# Grove_-_RGB_LED_Ring_20-WS2813_Mini.net
KiCad netlist of a schematic drawn in EAGLE
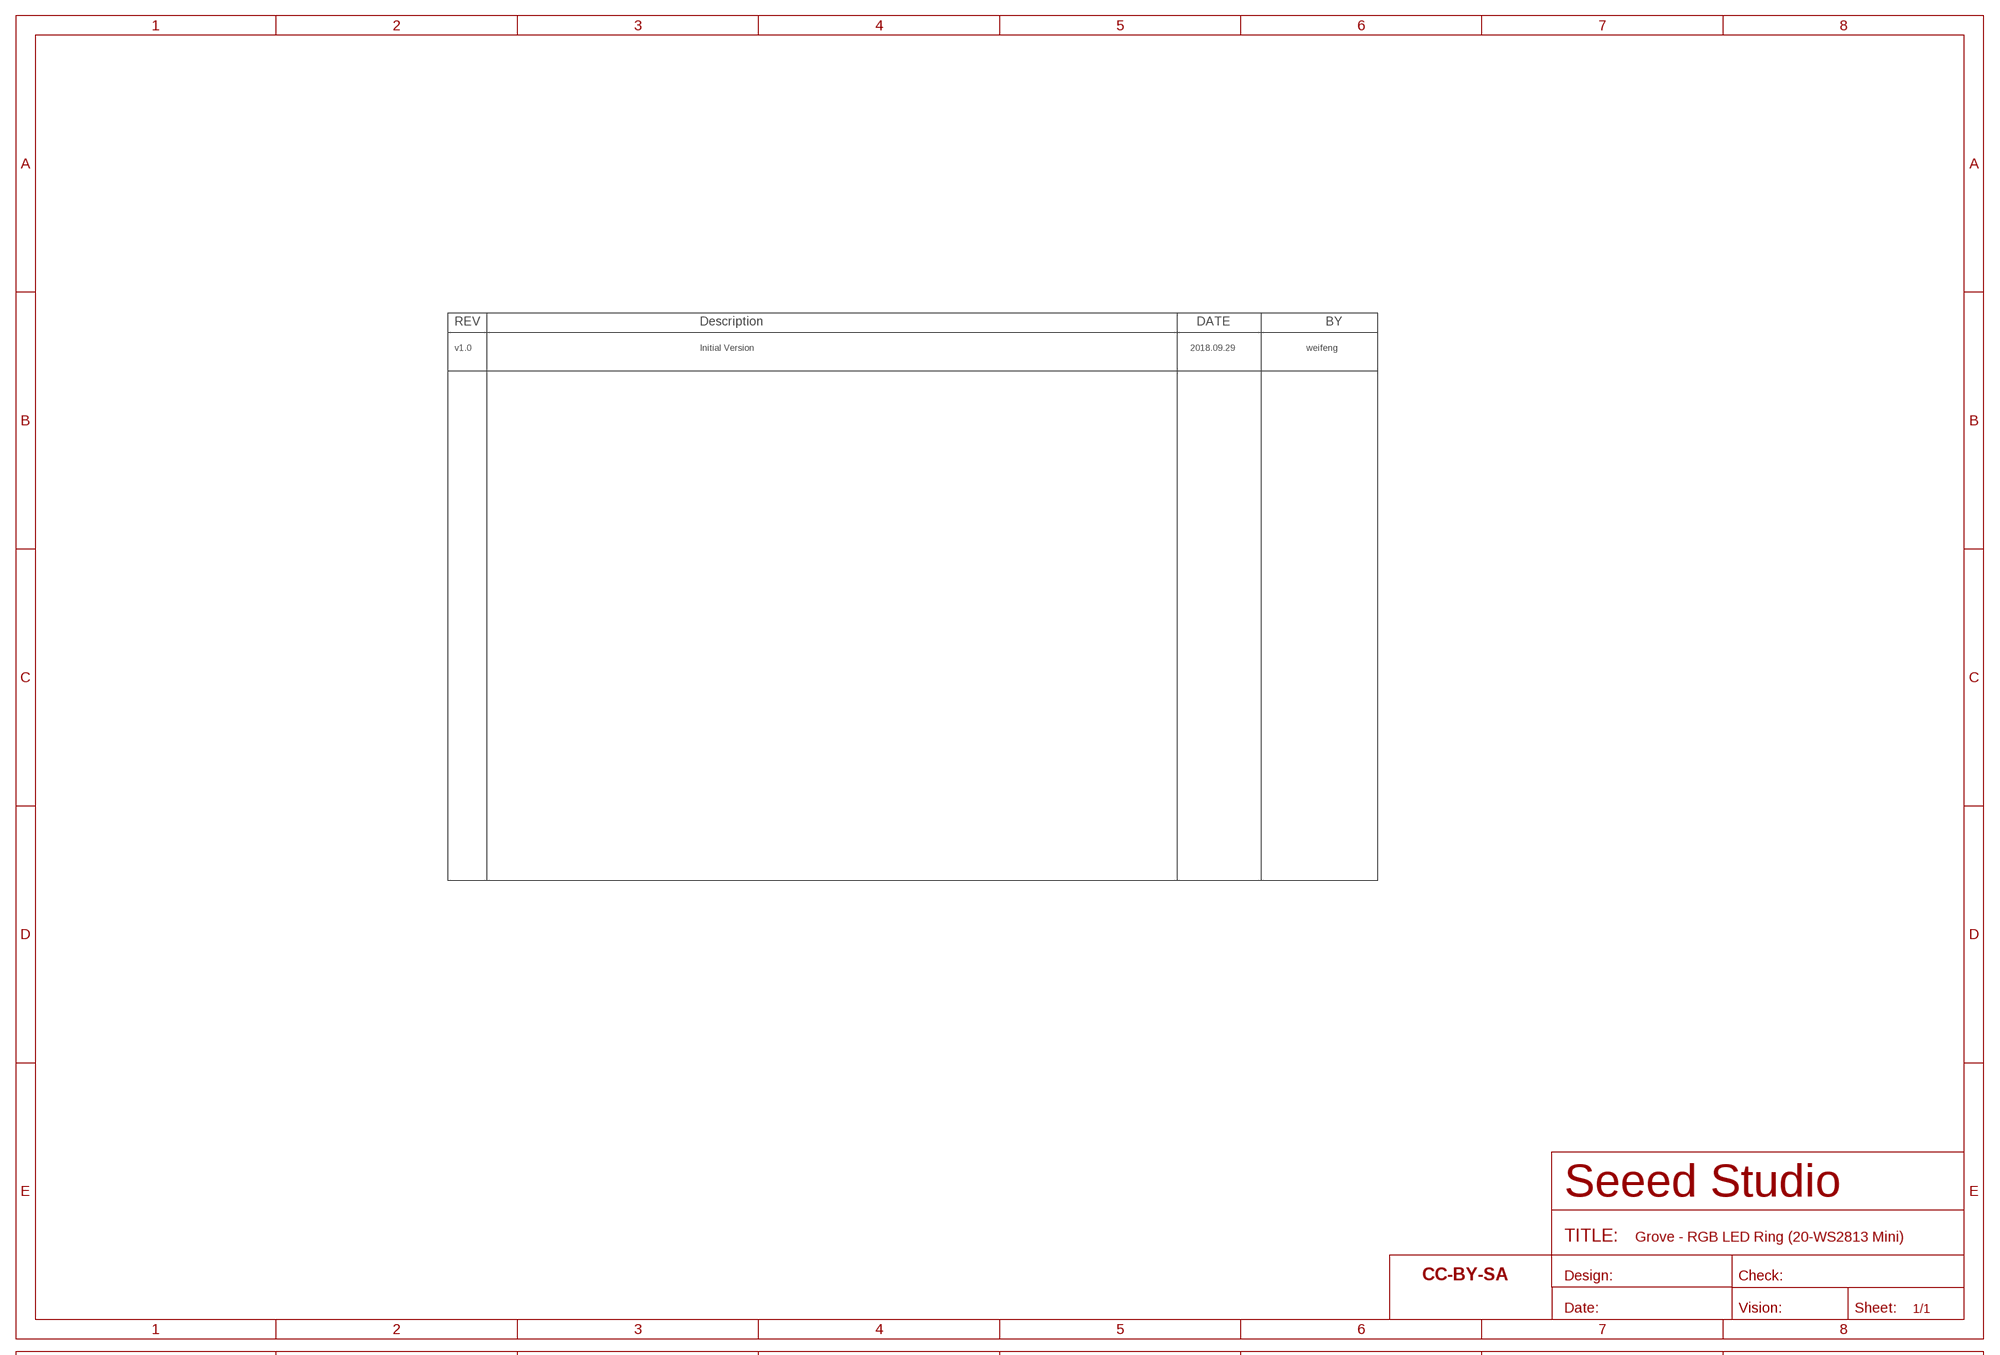
[diagram p0: schematic, sheet 1, part 1 of 2]
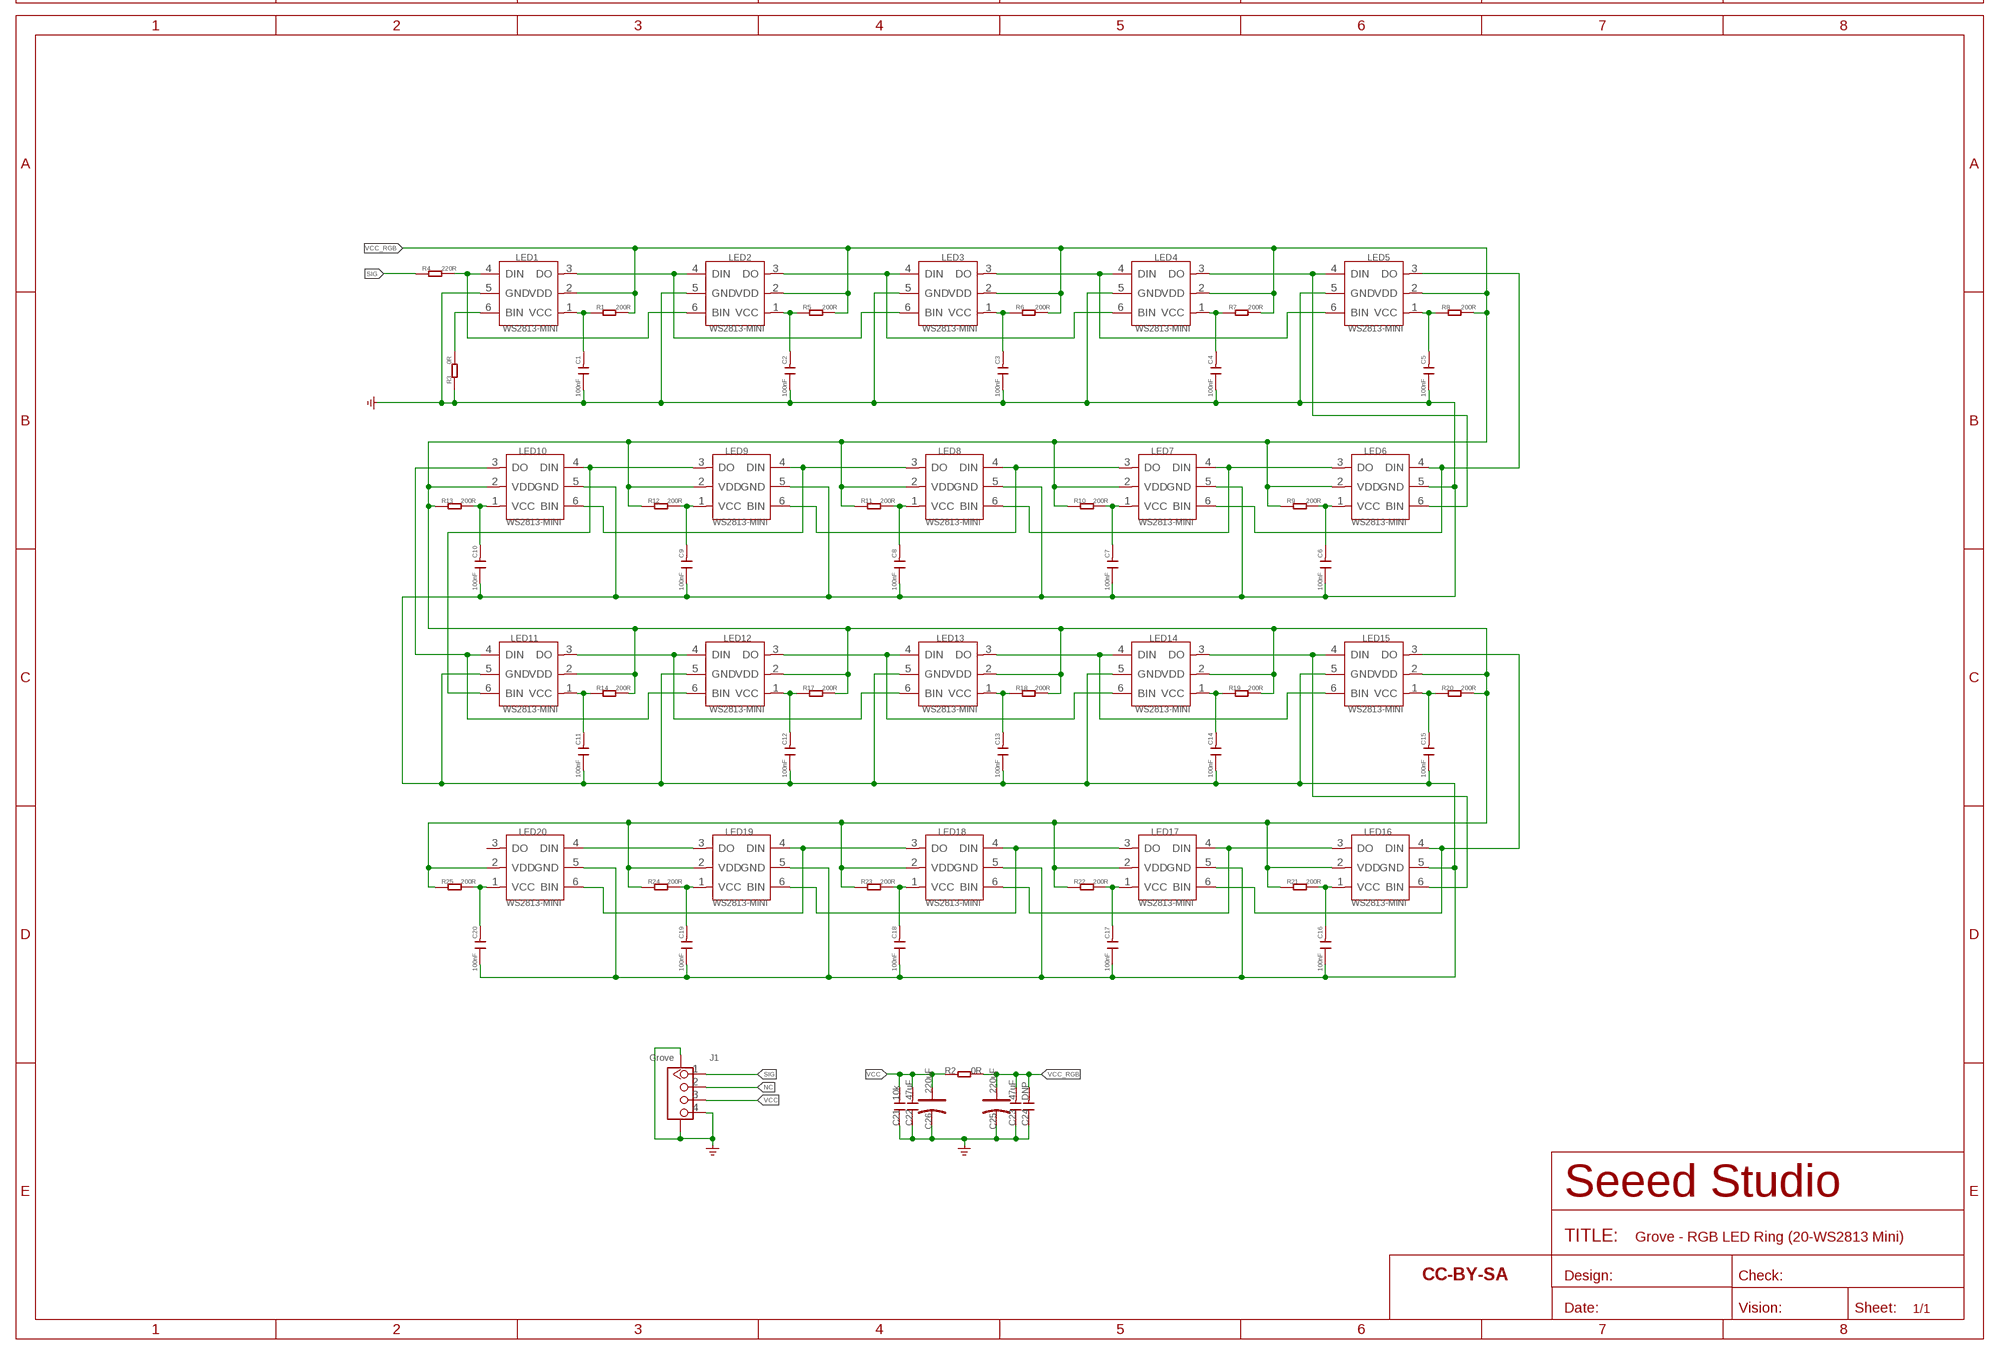
[diagram p1: schematic, sheet 1, part 2 of 2]

(export (version "E")
  (design (tool "Eeschema 10.0.6"))
  (components
    (comp (ref "C1")
      (value "100nF")
      (footprint "eagle-import:C0603")
      (libsource (lib "eagle-import") (part "C-0603"))
    )
    (comp (ref "C2")
      (value "100nF")
      (footprint "eagle-import:C0603")
      (libsource (lib "eagle-import") (part "C-0603"))
    )
    (comp (ref "C3")
      (value "100nF")
      (footprint "eagle-import:C0603")
      (libsource (lib "eagle-import") (part "C-0603"))
    )
    (comp (ref "C4")
      (value "100nF")
      (footprint "eagle-import:C0603")
      (libsource (lib "eagle-import") (part "C-0603"))
    )
    (comp (ref "C5")
      (value "100nF")
      (footprint "eagle-import:C0603")
      (libsource (lib "eagle-import") (part "C-0603"))
    )
    (comp (ref "C6")
      (value "100nF")
      (footprint "eagle-import:C0603")
      (libsource (lib "eagle-import") (part "C-0603"))
    )
    (comp (ref "C7")
      (value "100nF")
      (footprint "eagle-import:C0603")
      (libsource (lib "eagle-import") (part "C-0603"))
    )
    (comp (ref "C8")
      (value "100nF")
      (footprint "eagle-import:C0603")
      (libsource (lib "eagle-import") (part "C-0603"))
    )
    (comp (ref "C9")
      (value "100nF")
      (footprint "eagle-import:C0603")
      (libsource (lib "eagle-import") (part "C-0603"))
    )
    (comp (ref "C10")
      (value "100nF")
      (footprint "eagle-import:C0603")
      (libsource (lib "eagle-import") (part "C-0603"))
    )
    (comp (ref "C11")
      (value "100nF")
      (footprint "eagle-import:C0603")
      (libsource (lib "eagle-import") (part "C-0603"))
    )
    (comp (ref "C12")
      (value "100nF")
      (footprint "eagle-import:C0603")
      (libsource (lib "eagle-import") (part "C-0603"))
    )
    (comp (ref "C13")
      (value "100nF")
      (footprint "eagle-import:C0603")
      (libsource (lib "eagle-import") (part "C-0603"))
    )
    (comp (ref "C14")
      (value "100nF")
      (footprint "eagle-import:C0603")
      (libsource (lib "eagle-import") (part "C-0603"))
    )
    (comp (ref "C15")
      (value "100nF")
      (footprint "eagle-import:C0603")
      (libsource (lib "eagle-import") (part "C-0603"))
    )
    (comp (ref "C16")
      (value "100nF")
      (footprint "eagle-import:C0603")
      (libsource (lib "eagle-import") (part "C-0603"))
    )
    (comp (ref "C17")
      (value "100nF")
      (footprint "eagle-import:C0603")
      (libsource (lib "eagle-import") (part "C-0603"))
    )
    (comp (ref "C18")
      (value "100nF")
      (footprint "eagle-import:C0603")
      (libsource (lib "eagle-import") (part "C-0603"))
    )
    (comp (ref "C19")
      (value "100nF")
      (footprint "eagle-import:C0603")
      (libsource (lib "eagle-import") (part "C-0603"))
    )
    (comp (ref "C20")
      (value "100nF")
      (footprint "eagle-import:C0603")
      (libsource (lib "eagle-import") (part "C-0603"))
    )
    (comp (ref "C21")
      (value "10k")
      (footprint "eagle-import:C0603@1")
      (libsource (lib "eagle-import") (part "CAP-0603"))
    )
    (comp (ref "C22")
      (value "47uF")
      (footprint "eagle-import:C0805")
      (libsource (lib "eagle-import") (part "CAP-0805"))
    )
    (comp (ref "C23")
      (value "47uF")
      (footprint "eagle-import:C0805")
      (libsource (lib "eagle-import") (part "CAP-0805"))
    )
    (comp (ref "C24")
      (value "DNP")
      (footprint "eagle-import:C0603@1")
      (libsource (lib "eagle-import") (part "CAP-0603"))
    )
    (comp (ref "C25")
      (value "220uF")
      (footprint "eagle-import:AVX-B")
      (libsource (lib "eagle-import") (part "CAP-POLAR-AVX-B"))
    )
    (comp (ref "C26")
      (value "220uF")
      (footprint "eagle-import:AVX-B")
      (libsource (lib "eagle-import") (part "CAP-POLAR-AVX-B"))
    )
    (comp (ref "FR1")
      (value "SEEEDSTUDIO-OPEN-SCH-FRAME-BIG")
      (footprint "eagle-import:SEEEDSTUDIO-PCB-FRAME")
      (libsource (lib "eagle-import") (part "SEEEDSTUDIO-OPEN-SCH-FRAME-BIG"))
    )
    (comp (ref "FR2")
      (value "SEEEDSTUDIO-OPEN-SCH-FRAME-BIG")
      (footprint "eagle-import:SEEEDSTUDIO-PCB-FRAME")
      (libsource (lib "eagle-import") (part "SEEEDSTUDIO-OPEN-SCH-FRAME-BIG"))
    )
    (comp (ref "J1")
      (value "Grove")
      (footprint "eagle-import:HW4-SMD-2.0")
      (libsource (lib "eagle-import") (part "GROVE-CONNECTOR-SMD'DD'"))
    )
    (comp (ref "LED1")
      (value "WS2813-MINI")
      (footprint "eagle-import:LED6-1.1-3.5X3.5X0.95MM")
      (libsource (lib "eagle-import") (part "LED-RGB-6P-WS2813"))
    )
    (comp (ref "LED2")
      (value "WS2813-MINI")
      (footprint "eagle-import:LED6-1.1-3.5X3.5X0.95MM")
      (libsource (lib "eagle-import") (part "LED-RGB-6P-WS2813"))
    )
    (comp (ref "LED3")
      (value "WS2813-MINI")
      (footprint "eagle-import:LED6-1.1-3.5X3.5X0.95MM")
      (libsource (lib "eagle-import") (part "LED-RGB-6P-WS2813"))
    )
    (comp (ref "LED4")
      (value "WS2813-MINI")
      (footprint "eagle-import:LED6-1.1-3.5X3.5X0.95MM")
      (libsource (lib "eagle-import") (part "LED-RGB-6P-WS2813"))
    )
    (comp (ref "LED5")
      (value "WS2813-MINI")
      (footprint "eagle-import:LED6-1.1-3.5X3.5X0.95MM")
      (libsource (lib "eagle-import") (part "LED-RGB-6P-WS2813"))
    )
    (comp (ref "LED6")
      (value "WS2813-MINI")
      (footprint "eagle-import:LED6-1.1-3.5X3.5X0.95MM")
      (libsource (lib "eagle-import") (part "LED-RGB-6P-WS2813"))
    )
    (comp (ref "LED7")
      (value "WS2813-MINI")
      (footprint "eagle-import:LED6-1.1-3.5X3.5X0.95MM")
      (libsource (lib "eagle-import") (part "LED-RGB-6P-WS2813"))
    )
    (comp (ref "LED8")
      (value "WS2813-MINI")
      (footprint "eagle-import:LED6-1.1-3.5X3.5X0.95MM")
      (libsource (lib "eagle-import") (part "LED-RGB-6P-WS2813"))
    )
    (comp (ref "LED9")
      (value "WS2813-MINI")
      (footprint "eagle-import:LED6-1.1-3.5X3.5X0.95MM")
      (libsource (lib "eagle-import") (part "LED-RGB-6P-WS2813"))
    )
    (comp (ref "LED10")
      (value "WS2813-MINI")
      (footprint "eagle-import:LED6-1.1-3.5X3.5X0.95MM")
      (libsource (lib "eagle-import") (part "LED-RGB-6P-WS2813"))
    )
    (comp (ref "LED11")
      (value "WS2813-MINI")
      (footprint "eagle-import:LED6-1.1-3.5X3.5X0.95MM")
      (libsource (lib "eagle-import") (part "LED-RGB-6P-WS2813"))
    )
    (comp (ref "LED12")
      (value "WS2813-MINI")
      (footprint "eagle-import:LED6-1.1-3.5X3.5X0.95MM")
      (libsource (lib "eagle-import") (part "LED-RGB-6P-WS2813"))
    )
    (comp (ref "LED13")
      (value "WS2813-MINI")
      (footprint "eagle-import:LED6-1.1-3.5X3.5X0.95MM")
      (libsource (lib "eagle-import") (part "LED-RGB-6P-WS2813"))
    )
    (comp (ref "LED14")
      (value "WS2813-MINI")
      (footprint "eagle-import:LED6-1.1-3.5X3.5X0.95MM")
      (libsource (lib "eagle-import") (part "LED-RGB-6P-WS2813"))
    )
    (comp (ref "LED15")
      (value "WS2813-MINI")
      (footprint "eagle-import:LED6-1.1-3.5X3.5X0.95MM")
      (libsource (lib "eagle-import") (part "LED-RGB-6P-WS2813"))
    )
    (comp (ref "LED16")
      (value "WS2813-MINI")
      (footprint "eagle-import:LED6-1.1-3.5X3.5X0.95MM")
      (libsource (lib "eagle-import") (part "LED-RGB-6P-WS2813"))
    )
    (comp (ref "LED17")
      (value "WS2813-MINI")
      (footprint "eagle-import:LED6-1.1-3.5X3.5X0.95MM")
      (libsource (lib "eagle-import") (part "LED-RGB-6P-WS2813"))
    )
    (comp (ref "LED18")
      (value "WS2813-MINI")
      (footprint "eagle-import:LED6-1.1-3.5X3.5X0.95MM")
      (libsource (lib "eagle-import") (part "LED-RGB-6P-WS2813"))
    )
    (comp (ref "LED19")
      (value "WS2813-MINI")
      (footprint "eagle-import:LED6-1.1-3.5X3.5X0.95MM")
      (libsource (lib "eagle-import") (part "LED-RGB-6P-WS2813"))
    )
    (comp (ref "LED20")
      (value "WS2813-MINI")
      (footprint "eagle-import:LED6-1.1-3.5X3.5X0.95MM")
      (libsource (lib "eagle-import") (part "LED-RGB-6P-WS2813"))
    )
    (comp (ref "R1")
      (value "200R")
      (footprint "eagle-import:R0603")
      (libsource (lib "eagle-import") (part "R-0603"))
    )
    (comp (ref "R2")
      (value "0R")
      (footprint "eagle-import:R0805")
      (libsource (lib "eagle-import") (part "RES-0805"))
    )
    (comp (ref "R3")
      (value "0R")
      (footprint "eagle-import:R0603")
      (libsource (lib "eagle-import") (part "R-0603"))
    )
    (comp (ref "R4")
      (value "220R")
      (footprint "eagle-import:R0603")
      (libsource (lib "eagle-import") (part "R-0603"))
    )
    (comp (ref "R5")
      (value "200R")
      (footprint "eagle-import:R0603")
      (libsource (lib "eagle-import") (part "R-0603"))
    )
    (comp (ref "R6")
      (value "200R")
      (footprint "eagle-import:R0603")
      (libsource (lib "eagle-import") (part "R-0603"))
    )
    (comp (ref "R7")
      (value "200R")
      (footprint "eagle-import:R0603")
      (libsource (lib "eagle-import") (part "R-0603"))
    )
    (comp (ref "R8")
      (value "200R")
      (footprint "eagle-import:R0603")
      (libsource (lib "eagle-import") (part "R-0603"))
    )
    (comp (ref "R9")
      (value "200R")
      (footprint "eagle-import:R0603")
      (libsource (lib "eagle-import") (part "R-0603"))
    )
    (comp (ref "R10")
      (value "200R")
      (footprint "eagle-import:R0603")
      (libsource (lib "eagle-import") (part "R-0603"))
    )
    (comp (ref "R11")
      (value "200R")
      (footprint "eagle-import:R0603")
      (libsource (lib "eagle-import") (part "R-0603"))
    )
    (comp (ref "R12")
      (value "200R")
      (footprint "eagle-import:R0603")
      (libsource (lib "eagle-import") (part "R-0603"))
    )
    (comp (ref "R13")
      (value "200R")
      (footprint "eagle-import:R0603")
      (libsource (lib "eagle-import") (part "R-0603"))
    )
    (comp (ref "R14")
      (value "200R")
      (footprint "eagle-import:R0603")
      (libsource (lib "eagle-import") (part "R-0603"))
    )
    (comp (ref "R17")
      (value "200R")
      (footprint "eagle-import:R0603")
      (libsource (lib "eagle-import") (part "R-0603"))
    )
    (comp (ref "R18")
      (value "200R")
      (footprint "eagle-import:R0603")
      (libsource (lib "eagle-import") (part "R-0603"))
    )
    (comp (ref "R19")
      (value "200R")
      (footprint "eagle-import:R0603")
      (libsource (lib "eagle-import") (part "R-0603"))
    )
    (comp (ref "R20")
      (value "200R")
      (footprint "eagle-import:R0603")
      (libsource (lib "eagle-import") (part "R-0603"))
    )
    (comp (ref "R21")
      (value "200R")
      (footprint "eagle-import:R0603")
      (libsource (lib "eagle-import") (part "R-0603"))
    )
    (comp (ref "R22")
      (value "200R")
      (footprint "eagle-import:R0603")
      (libsource (lib "eagle-import") (part "R-0603"))
    )
    (comp (ref "R23")
      (value "200R")
      (footprint "eagle-import:R0603")
      (libsource (lib "eagle-import") (part "R-0603"))
    )
    (comp (ref "R24")
      (value "200R")
      (footprint "eagle-import:R0603")
      (libsource (lib "eagle-import") (part "R-0603"))
    )
    (comp (ref "R25")
      (value "200R")
      (footprint "eagle-import:R0603")
      (libsource (lib "eagle-import") (part "R-0603"))
    )
  )
  (nets
    (net (code "1") (name "GND_POWER") (class "Default")
      (node (ref "C1") (pin "1") (pinfunction "1_1") (pintype "passive"))
      (node (ref "C10") (pin "1") (pinfunction "1_1") (pintype "passive"))
      (node (ref "C11") (pin "1") (pinfunction "1_1") (pintype "passive"))
      (node (ref "C12") (pin "1") (pinfunction "1_1") (pintype "passive"))
      (node (ref "C13") (pin "1") (pinfunction "1_1") (pintype "passive"))
      (node (ref "C14") (pin "1") (pinfunction "1_1") (pintype "passive"))
      (node (ref "C15") (pin "1") (pinfunction "1_1") (pintype "passive"))
      (node (ref "C16") (pin "1") (pinfunction "1_1") (pintype "passive"))
      (node (ref "C17") (pin "1") (pinfunction "1_1") (pintype "passive"))
      (node (ref "C18") (pin "1") (pinfunction "1_1") (pintype "passive"))
      (node (ref "C19") (pin "1") (pinfunction "1_1") (pintype "passive"))
      (node (ref "C2") (pin "1") (pinfunction "1_1") (pintype "passive"))
      (node (ref "C20") (pin "1") (pinfunction "1_1") (pintype "passive"))
      (node (ref "C21") (pin "1") (pinfunction "1_1") (pintype "passive"))
      (node (ref "C22") (pin "1") (pinfunction "1_1") (pintype "passive"))
      (node (ref "C23") (pin "1") (pinfunction "1_1") (pintype "passive"))
      (node (ref "C24") (pin "1") (pinfunction "1_1") (pintype "passive"))
      (node (ref "C25") (pin "-") (pinfunction "-_-") (pintype "passive"))
      (node (ref "C26") (pin "-") (pinfunction "-_-") (pintype "passive"))
      (node (ref "C3") (pin "1") (pinfunction "1_1") (pintype "passive"))
      (node (ref "C4") (pin "1") (pinfunction "1_1") (pintype "passive"))
      (node (ref "C5") (pin "1") (pinfunction "1_1") (pintype "passive"))
      (node (ref "C6") (pin "1") (pinfunction "1_1") (pintype "passive"))
      (node (ref "C7") (pin "1") (pinfunction "1_1") (pintype "passive"))
      (node (ref "C8") (pin "1") (pinfunction "1_1") (pintype "passive"))
      (node (ref "C9") (pin "1") (pinfunction "1_1") (pintype "passive"))
      (node (ref "J1") (pin "4") (pinfunction "4_4") (pintype "bidirectional"))
      (node (ref "J1") (pin "SS1") (pinfunction "SS1_SS1") (pintype "bidirectional"))
      (node (ref "J1") (pin "SS2") (pinfunction "SS2_SS2") (pintype "bidirectional"))
      (node (ref "LED1") (pin "5") (pinfunction "GND_5") (pintype "bidirectional"))
      (node (ref "LED10") (pin "5") (pinfunction "GND_5") (pintype "bidirectional"))
      (node (ref "LED11") (pin "5") (pinfunction "GND_5") (pintype "bidirectional"))
      (node (ref "LED12") (pin "5") (pinfunction "GND_5") (pintype "bidirectional"))
      (node (ref "LED13") (pin "5") (pinfunction "GND_5") (pintype "bidirectional"))
      (node (ref "LED14") (pin "5") (pinfunction "GND_5") (pintype "bidirectional"))
      (node (ref "LED15") (pin "5") (pinfunction "GND_5") (pintype "bidirectional"))
      (node (ref "LED16") (pin "5") (pinfunction "GND_5") (pintype "bidirectional"))
      (node (ref "LED17") (pin "5") (pinfunction "GND_5") (pintype "bidirectional"))
      (node (ref "LED18") (pin "5") (pinfunction "GND_5") (pintype "bidirectional"))
      (node (ref "LED19") (pin "5") (pinfunction "GND_5") (pintype "bidirectional"))
      (node (ref "LED2") (pin "5") (pinfunction "GND_5") (pintype "bidirectional"))
      (node (ref "LED20") (pin "5") (pinfunction "GND_5") (pintype "bidirectional"))
      (node (ref "LED3") (pin "5") (pinfunction "GND_5") (pintype "bidirectional"))
      (node (ref "LED4") (pin "5") (pinfunction "GND_5") (pintype "bidirectional"))
      (node (ref "LED5") (pin "5") (pinfunction "GND_5") (pintype "bidirectional"))
      (node (ref "LED6") (pin "5") (pinfunction "GND_5") (pintype "bidirectional"))
      (node (ref "LED7") (pin "5") (pinfunction "GND_5") (pintype "bidirectional"))
      (node (ref "LED8") (pin "5") (pinfunction "GND_5") (pintype "bidirectional"))
      (node (ref "LED9") (pin "5") (pinfunction "GND_5") (pintype "bidirectional"))
      (node (ref "R3") (pin "1") (pinfunction "1_1") (pintype "passive"))
    )
    (net (code "2") (name "NC") (class "Default")
      (node (ref "J1") (pin "2") (pinfunction "2_2") (pintype "bidirectional"))
    )
    (net (code "3") (name "Net-(LED1-BIN)") (class "Default")
      (node (ref "LED1") (pin "6") (pinfunction "BIN_6") (pintype "bidirectional"))
      (node (ref "R3") (pin "2") (pinfunction "2_2") (pintype "passive"))
    )
    (net (code "4") (name "Net-(LED1-DIN)") (class "Default")
      (node (ref "LED1") (pin "4") (pinfunction "DIN_4") (pintype "bidirectional"))
      (node (ref "LED2") (pin "6") (pinfunction "BIN_6") (pintype "bidirectional"))
      (node (ref "R4") (pin "2") (pinfunction "2_2") (pintype "passive"))
    )
    (net (code "5") (name "Net-(LED1-DO)") (class "Default")
      (node (ref "LED1") (pin "3") (pinfunction "DO_3") (pintype "bidirectional"))
      (node (ref "LED2") (pin "4") (pinfunction "DIN_4") (pintype "bidirectional"))
      (node (ref "LED3") (pin "6") (pinfunction "BIN_6") (pintype "bidirectional"))
    )
    (net (code "6") (name "Net-(LED1-VCC)") (class "Default")
      (node (ref "C1") (pin "2") (pinfunction "2_2") (pintype "passive"))
      (node (ref "LED1") (pin "1") (pinfunction "VCC_1") (pintype "bidirectional"))
      (node (ref "R1") (pin "1") (pinfunction "1_1") (pintype "passive"))
    )
    (net (code "7") (name "Net-(LED2-DO)") (class "Default")
      (node (ref "LED2") (pin "3") (pinfunction "DO_3") (pintype "bidirectional"))
      (node (ref "LED3") (pin "4") (pinfunction "DIN_4") (pintype "bidirectional"))
      (node (ref "LED4") (pin "6") (pinfunction "BIN_6") (pintype "bidirectional"))
    )
    (net (code "8") (name "Net-(LED2-VCC)") (class "Default")
      (node (ref "C2") (pin "2") (pinfunction "2_2") (pintype "passive"))
      (node (ref "LED2") (pin "1") (pinfunction "VCC_1") (pintype "bidirectional"))
      (node (ref "R5") (pin "1") (pinfunction "1_1") (pintype "passive"))
    )
    (net (code "9") (name "Net-(LED3-DO)") (class "Default")
      (node (ref "LED3") (pin "3") (pinfunction "DO_3") (pintype "bidirectional"))
      (node (ref "LED4") (pin "4") (pinfunction "DIN_4") (pintype "bidirectional"))
      (node (ref "LED5") (pin "6") (pinfunction "BIN_6") (pintype "bidirectional"))
    )
    (net (code "10") (name "Net-(LED3-VCC)") (class "Default")
      (node (ref "C3") (pin "2") (pinfunction "2_2") (pintype "passive"))
      (node (ref "LED3") (pin "1") (pinfunction "VCC_1") (pintype "bidirectional"))
      (node (ref "R6") (pin "1") (pinfunction "1_1") (pintype "passive"))
    )
    (net (code "11") (name "Net-(LED4-DO)") (class "Default")
      (node (ref "LED4") (pin "3") (pinfunction "DO_3") (pintype "bidirectional"))
      (node (ref "LED5") (pin "4") (pinfunction "DIN_4") (pintype "bidirectional"))
      (node (ref "LED6") (pin "6") (pinfunction "BIN_6") (pintype "bidirectional"))
    )
    (net (code "12") (name "Net-(LED4-VCC)") (class "Default")
      (node (ref "C4") (pin "2") (pinfunction "2_2") (pintype "passive"))
      (node (ref "LED4") (pin "1") (pinfunction "VCC_1") (pintype "bidirectional"))
      (node (ref "R7") (pin "1") (pinfunction "1_1") (pintype "passive"))
    )
    (net (code "13") (name "Net-(LED5-DO)") (class "Default")
      (node (ref "LED5") (pin "3") (pinfunction "DO_3") (pintype "bidirectional"))
      (node (ref "LED6") (pin "4") (pinfunction "DIN_4") (pintype "bidirectional"))
      (node (ref "LED7") (pin "6") (pinfunction "BIN_6") (pintype "bidirectional"))
    )
    (net (code "14") (name "Net-(LED5-VCC)") (class "Default")
      (node (ref "C5") (pin "2") (pinfunction "2_2") (pintype "passive"))
      (node (ref "LED5") (pin "1") (pinfunction "VCC_1") (pintype "bidirectional"))
      (node (ref "R8") (pin "1") (pinfunction "1_1") (pintype "passive"))
    )
    (net (code "15") (name "Net-(LED6-DO)") (class "Default")
      (node (ref "LED6") (pin "3") (pinfunction "DO_3") (pintype "bidirectional"))
      (node (ref "LED7") (pin "4") (pinfunction "DIN_4") (pintype "bidirectional"))
      (node (ref "LED8") (pin "6") (pinfunction "BIN_6") (pintype "bidirectional"))
    )
    (net (code "16") (name "Net-(LED6-VCC)") (class "Default")
      (node (ref "C6") (pin "2") (pinfunction "2_2") (pintype "passive"))
      (node (ref "LED6") (pin "1") (pinfunction "VCC_1") (pintype "bidirectional"))
      (node (ref "R9") (pin "2") (pinfunction "2_2") (pintype "passive"))
    )
    (net (code "17") (name "Net-(LED7-DO)") (class "Default")
      (node (ref "LED7") (pin "3") (pinfunction "DO_3") (pintype "bidirectional"))
      (node (ref "LED8") (pin "4") (pinfunction "DIN_4") (pintype "bidirectional"))
      (node (ref "LED9") (pin "6") (pinfunction "BIN_6") (pintype "bidirectional"))
    )
    (net (code "18") (name "Net-(LED7-VCC)") (class "Default")
      (node (ref "C7") (pin "2") (pinfunction "2_2") (pintype "passive"))
      (node (ref "LED7") (pin "1") (pinfunction "VCC_1") (pintype "bidirectional"))
      (node (ref "R10") (pin "2") (pinfunction "2_2") (pintype "passive"))
    )
    (net (code "19") (name "Net-(LED8-VCC)") (class "Default")
      (node (ref "C8") (pin "2") (pinfunction "2_2") (pintype "passive"))
      (node (ref "LED8") (pin "1") (pinfunction "VCC_1") (pintype "bidirectional"))
      (node (ref "R11") (pin "2") (pinfunction "2_2") (pintype "passive"))
    )
    (net (code "20") (name "Net-(LED9-VCC)") (class "Default")
      (node (ref "C9") (pin "2") (pinfunction "2_2") (pintype "passive"))
      (node (ref "LED9") (pin "1") (pinfunction "VCC_1") (pintype "bidirectional"))
      (node (ref "R12") (pin "2") (pinfunction "2_2") (pintype "passive"))
    )
    (net (code "21") (name "Net-(LED10-BIN)") (class "Default")
      (node (ref "LED10") (pin "6") (pinfunction "BIN_6") (pintype "bidirectional"))
      (node (ref "LED8") (pin "3") (pinfunction "DO_3") (pintype "bidirectional"))
      (node (ref "LED9") (pin "4") (pinfunction "DIN_4") (pintype "bidirectional"))
    )
    (net (code "22") (name "Net-(LED10-DIN)") (class "Default")
      (node (ref "LED10") (pin "4") (pinfunction "DIN_4") (pintype "bidirectional"))
      (node (ref "LED11") (pin "6") (pinfunction "BIN_6") (pintype "bidirectional"))
      (node (ref "LED9") (pin "3") (pinfunction "DO_3") (pintype "bidirectional"))
    )
    (net (code "23") (name "Net-(LED10-DO)") (class "Default")
      (node (ref "LED10") (pin "3") (pinfunction "DO_3") (pintype "bidirectional"))
      (node (ref "LED11") (pin "4") (pinfunction "DIN_4") (pintype "bidirectional"))
      (node (ref "LED12") (pin "6") (pinfunction "BIN_6") (pintype "bidirectional"))
    )
    (net (code "24") (name "Net-(LED10-VCC)") (class "Default")
      (node (ref "C10") (pin "2") (pinfunction "2_2") (pintype "passive"))
      (node (ref "LED10") (pin "1") (pinfunction "VCC_1") (pintype "bidirectional"))
      (node (ref "R13") (pin "2") (pinfunction "2_2") (pintype "passive"))
    )
    (net (code "25") (name "Net-(LED11-DO)") (class "Default")
      (node (ref "LED11") (pin "3") (pinfunction "DO_3") (pintype "bidirectional"))
      (node (ref "LED12") (pin "4") (pinfunction "DIN_4") (pintype "bidirectional"))
      (node (ref "LED13") (pin "6") (pinfunction "BIN_6") (pintype "bidirectional"))
    )
    (net (code "26") (name "Net-(LED11-VCC)") (class "Default")
      (node (ref "C11") (pin "2") (pinfunction "2_2") (pintype "passive"))
      (node (ref "LED11") (pin "1") (pinfunction "VCC_1") (pintype "bidirectional"))
      (node (ref "R14") (pin "1") (pinfunction "1_1") (pintype "passive"))
    )
    (net (code "27") (name "Net-(LED12-DO)") (class "Default")
      (node (ref "LED12") (pin "3") (pinfunction "DO_3") (pintype "bidirectional"))
      (node (ref "LED13") (pin "4") (pinfunction "DIN_4") (pintype "bidirectional"))
      (node (ref "LED14") (pin "6") (pinfunction "BIN_6") (pintype "bidirectional"))
    )
    (net (code "28") (name "Net-(LED12-VCC)") (class "Default")
      (node (ref "C12") (pin "2") (pinfunction "2_2") (pintype "passive"))
      (node (ref "LED12") (pin "1") (pinfunction "VCC_1") (pintype "bidirectional"))
      (node (ref "R17") (pin "1") (pinfunction "1_1") (pintype "passive"))
    )
    (net (code "29") (name "Net-(LED13-DO)") (class "Default")
      (node (ref "LED13") (pin "3") (pinfunction "DO_3") (pintype "bidirectional"))
      (node (ref "LED14") (pin "4") (pinfunction "DIN_4") (pintype "bidirectional"))
      (node (ref "LED15") (pin "6") (pinfunction "BIN_6") (pintype "bidirectional"))
    )
    (net (code "30") (name "Net-(LED13-VCC)") (class "Default")
      (node (ref "C13") (pin "2") (pinfunction "2_2") (pintype "passive"))
      (node (ref "LED13") (pin "1") (pinfunction "VCC_1") (pintype "bidirectional"))
      (node (ref "R18") (pin "1") (pinfunction "1_1") (pintype "passive"))
    )
    (net (code "31") (name "Net-(LED14-DO)") (class "Default")
      (node (ref "LED14") (pin "3") (pinfunction "DO_3") (pintype "bidirectional"))
      (node (ref "LED15") (pin "4") (pinfunction "DIN_4") (pintype "bidirectional"))
      (node (ref "LED16") (pin "6") (pinfunction "BIN_6") (pintype "bidirectional"))
    )
    (net (code "32") (name "Net-(LED14-VCC)") (class "Default")
      (node (ref "C14") (pin "2") (pinfunction "2_2") (pintype "passive"))
      (node (ref "LED14") (pin "1") (pinfunction "VCC_1") (pintype "bidirectional"))
      (node (ref "R19") (pin "1") (pinfunction "1_1") (pintype "passive"))
    )
    (net (code "33") (name "Net-(LED15-DO)") (class "Default")
      (node (ref "LED15") (pin "3") (pinfunction "DO_3") (pintype "bidirectional"))
      (node (ref "LED16") (pin "4") (pinfunction "DIN_4") (pintype "bidirectional"))
      (node (ref "LED17") (pin "6") (pinfunction "BIN_6") (pintype "bidirectional"))
    )
    (net (code "34") (name "Net-(LED15-VCC)") (class "Default")
      (node (ref "C15") (pin "2") (pinfunction "2_2") (pintype "passive"))
      (node (ref "LED15") (pin "1") (pinfunction "VCC_1") (pintype "bidirectional"))
      (node (ref "R20") (pin "1") (pinfunction "1_1") (pintype "passive"))
    )
    (net (code "35") (name "Net-(LED16-DO)") (class "Default")
      (node (ref "LED16") (pin "3") (pinfunction "DO_3") (pintype "bidirectional"))
      (node (ref "LED17") (pin "4") (pinfunction "DIN_4") (pintype "bidirectional"))
      (node (ref "LED18") (pin "6") (pinfunction "BIN_6") (pintype "bidirectional"))
    )
    (net (code "36") (name "Net-(LED16-VCC)") (class "Default")
      (node (ref "C16") (pin "2") (pinfunction "2_2") (pintype "passive"))
      (node (ref "LED16") (pin "1") (pinfunction "VCC_1") (pintype "bidirectional"))
      (node (ref "R21") (pin "2") (pinfunction "2_2") (pintype "passive"))
    )
    (net (code "37") (name "Net-(LED17-DO)") (class "Default")
      (node (ref "LED17") (pin "3") (pinfunction "DO_3") (pintype "bidirectional"))
      (node (ref "LED18") (pin "4") (pinfunction "DIN_4") (pintype "bidirectional"))
      (node (ref "LED19") (pin "6") (pinfunction "BIN_6") (pintype "bidirectional"))
    )
    (net (code "38") (name "Net-(LED17-VCC)") (class "Default")
      (node (ref "C17") (pin "2") (pinfunction "2_2") (pintype "passive"))
      (node (ref "LED17") (pin "1") (pinfunction "VCC_1") (pintype "bidirectional"))
      (node (ref "R22") (pin "2") (pinfunction "2_2") (pintype "passive"))
    )
    (net (code "39") (name "Net-(LED18-DO)") (class "Default")
      (node (ref "LED18") (pin "3") (pinfunction "DO_3") (pintype "bidirectional"))
      (node (ref "LED19") (pin "4") (pinfunction "DIN_4") (pintype "bidirectional"))
      (node (ref "LED20") (pin "6") (pinfunction "BIN_6") (pintype "bidirectional"))
    )
    (net (code "40") (name "Net-(LED18-VCC)") (class "Default")
      (node (ref "C18") (pin "2") (pinfunction "2_2") (pintype "passive"))
      (node (ref "LED18") (pin "1") (pinfunction "VCC_1") (pintype "bidirectional"))
      (node (ref "R23") (pin "2") (pinfunction "2_2") (pintype "passive"))
    )
    (net (code "41") (name "Net-(LED19-DO)") (class "Default")
      (node (ref "LED19") (pin "3") (pinfunction "DO_3") (pintype "bidirectional"))
      (node (ref "LED20") (pin "4") (pinfunction "DIN_4") (pintype "bidirectional"))
    )
    (net (code "42") (name "Net-(LED19-VCC)") (class "Default")
      (node (ref "C19") (pin "2") (pinfunction "2_2") (pintype "passive"))
      (node (ref "LED19") (pin "1") (pinfunction "VCC_1") (pintype "bidirectional"))
      (node (ref "R24") (pin "2") (pinfunction "2_2") (pintype "passive"))
    )
    (net (code "43") (name "Net-(LED20-VCC)") (class "Default")
      (node (ref "C20") (pin "2") (pinfunction "2_2") (pintype "passive"))
      (node (ref "LED20") (pin "1") (pinfunction "VCC_1") (pintype "bidirectional"))
      (node (ref "R25") (pin "2") (pinfunction "2_2") (pintype "passive"))
    )
    (net (code "44") (name "SIG") (class "Default")
      (node (ref "J1") (pin "1") (pinfunction "1_1") (pintype "bidirectional"))
      (node (ref "R4") (pin "1") (pinfunction "1_1") (pintype "passive"))
    )
    (net (code "45") (name "VCC") (class "Default")
      (node (ref "C21") (pin "2") (pinfunction "2_2") (pintype "passive"))
      (node (ref "C22") (pin "2") (pinfunction "2_2") (pintype "passive"))
      (node (ref "C26") (pin "+") (pinfunction "+_+") (pintype "passive"))
      (node (ref "J1") (pin "3") (pinfunction "3_3") (pintype "bidirectional"))
      (node (ref "R2") (pin "1") (pinfunction "1_1") (pintype "passive"))
    )
    (net (code "46") (name "VCC_RGB") (class "Default")
      (node (ref "C23") (pin "2") (pinfunction "2_2") (pintype "passive"))
      (node (ref "C24") (pin "2") (pinfunction "2_2") (pintype "passive"))
      (node (ref "C25") (pin "+") (pinfunction "+_+") (pintype "passive"))
      (node (ref "LED1") (pin "2") (pinfunction "VDD_2") (pintype "bidirectional"))
      (node (ref "LED10") (pin "2") (pinfunction "VDD_2") (pintype "bidirectional"))
      (node (ref "LED11") (pin "2") (pinfunction "VDD_2") (pintype "bidirectional"))
      (node (ref "LED12") (pin "2") (pinfunction "VDD_2") (pintype "bidirectional"))
      (node (ref "LED13") (pin "2") (pinfunction "VDD_2") (pintype "bidirectional"))
      (node (ref "LED14") (pin "2") (pinfunction "VDD_2") (pintype "bidirectional"))
      (node (ref "LED15") (pin "2") (pinfunction "VDD_2") (pintype "bidirectional"))
      (node (ref "LED16") (pin "2") (pinfunction "VDD_2") (pintype "bidirectional"))
      (node (ref "LED17") (pin "2") (pinfunction "VDD_2") (pintype "bidirectional"))
      (node (ref "LED18") (pin "2") (pinfunction "VDD_2") (pintype "bidirectional"))
      (node (ref "LED19") (pin "2") (pinfunction "VDD_2") (pintype "bidirectional"))
      (node (ref "LED2") (pin "2") (pinfunction "VDD_2") (pintype "bidirectional"))
      (node (ref "LED20") (pin "2") (pinfunction "VDD_2") (pintype "bidirectional"))
      (node (ref "LED3") (pin "2") (pinfunction "VDD_2") (pintype "bidirectional"))
      (node (ref "LED4") (pin "2") (pinfunction "VDD_2") (pintype "bidirectional"))
      (node (ref "LED5") (pin "2") (pinfunction "VDD_2") (pintype "bidirectional"))
      (node (ref "LED6") (pin "2") (pinfunction "VDD_2") (pintype "bidirectional"))
      (node (ref "LED7") (pin "2") (pinfunction "VDD_2") (pintype "bidirectional"))
      (node (ref "LED8") (pin "2") (pinfunction "VDD_2") (pintype "bidirectional"))
      (node (ref "LED9") (pin "2") (pinfunction "VDD_2") (pintype "bidirectional"))
      (node (ref "R1") (pin "2") (pinfunction "2_2") (pintype "passive"))
      (node (ref "R10") (pin "1") (pinfunction "1_1") (pintype "passive"))
      (node (ref "R11") (pin "1") (pinfunction "1_1") (pintype "passive"))
      (node (ref "R12") (pin "1") (pinfunction "1_1") (pintype "passive"))
      (node (ref "R13") (pin "1") (pinfunction "1_1") (pintype "passive"))
      (node (ref "R14") (pin "2") (pinfunction "2_2") (pintype "passive"))
      (node (ref "R17") (pin "2") (pinfunction "2_2") (pintype "passive"))
      (node (ref "R18") (pin "2") (pinfunction "2_2") (pintype "passive"))
      (node (ref "R19") (pin "2") (pinfunction "2_2") (pintype "passive"))
      (node (ref "R2") (pin "2") (pinfunction "2_2") (pintype "passive"))
      (node (ref "R20") (pin "2") (pinfunction "2_2") (pintype "passive"))
      (node (ref "R21") (pin "1") (pinfunction "1_1") (pintype "passive"))
      (node (ref "R22") (pin "1") (pinfunction "1_1") (pintype "passive"))
      (node (ref "R23") (pin "1") (pinfunction "1_1") (pintype "passive"))
      (node (ref "R24") (pin "1") (pinfunction "1_1") (pintype "passive"))
      (node (ref "R25") (pin "1") (pinfunction "1_1") (pintype "passive"))
      (node (ref "R5") (pin "2") (pinfunction "2_2") (pintype "passive"))
      (node (ref "R6") (pin "2") (pinfunction "2_2") (pintype "passive"))
      (node (ref "R7") (pin "2") (pinfunction "2_2") (pintype "passive"))
      (node (ref "R8") (pin "2") (pinfunction "2_2") (pintype "passive"))
      (node (ref "R9") (pin "1") (pinfunction "1_1") (pintype "passive"))
    )
    (net (code "47") (name "unconnected-(LED20-DO-Pad3)") (class "Default")
      (node (ref "LED20") (pin "3") (pinfunction "DO_3") (pintype "bidirectional"))
    )
  )
)
